# main.net
KiCad netlist of a schematic drawn in Altium Designer
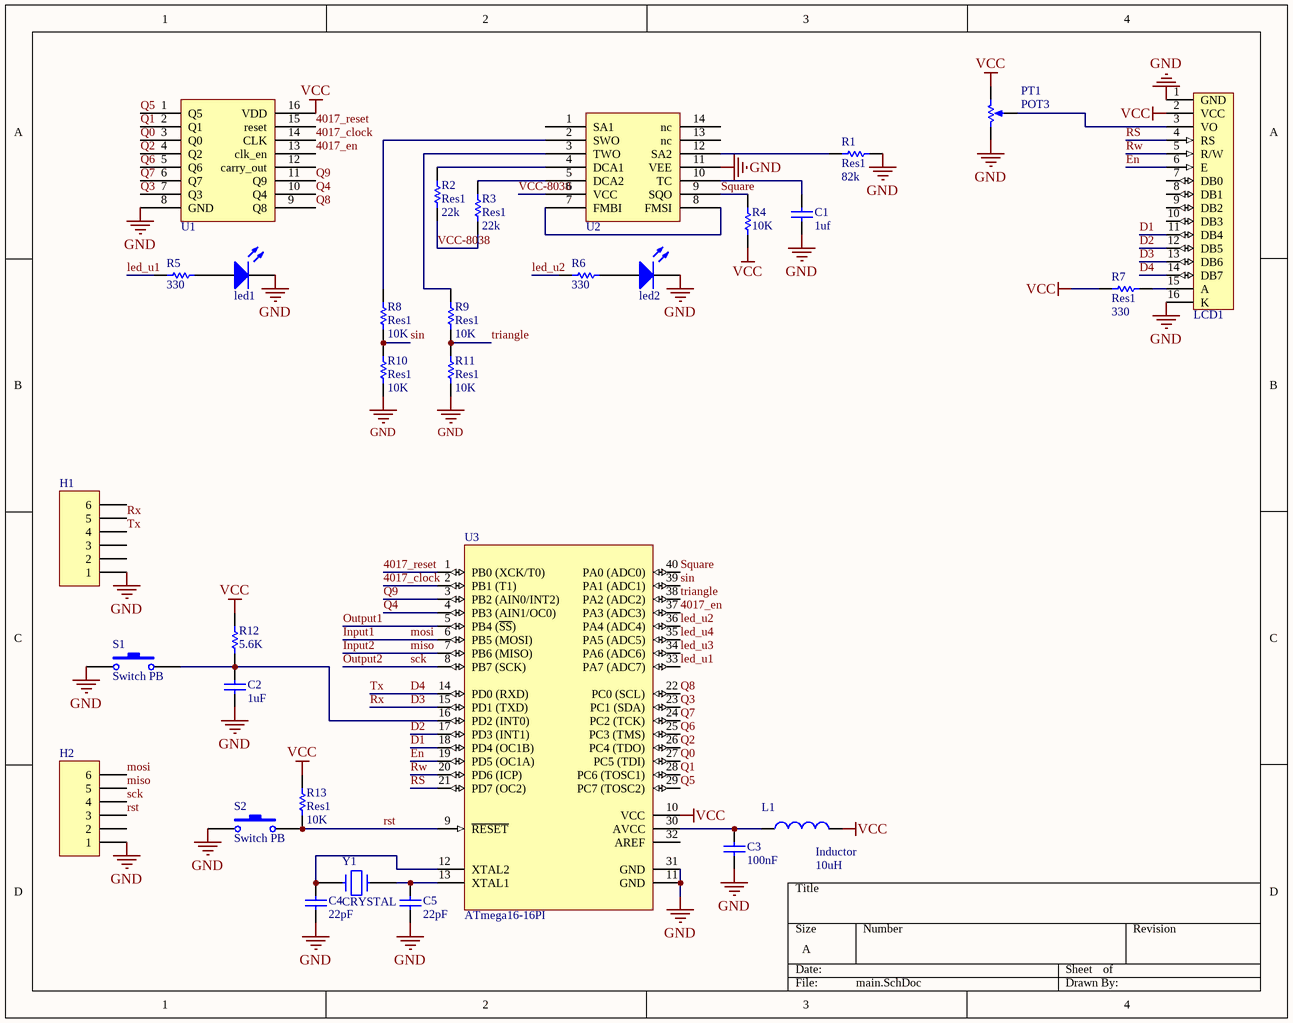
[diagram p0: main.SchDoc]

(export (version "E")
  (design (tool "Eeschema 10.0.6"))
  (components
    (comp (ref "C1")
      (value "1uf")
      (footprint "My_cap100n")
      (description "Capacitor")
      (fields (field (name "Comment") "Cap-NF") (field (name "PUBLISHER") "Altium Limited"))
      (libsource (lib "Mine-Discreet") (part "Cap-NF"))
    )
    (comp (ref "C2")
      (value "1uF")
      (footprint "My_cap100n")
      (description "Capacitor")
      (fields (field (name "Comment") "Cap-NF") (field (name "PUBLISHER") "Altium Limited"))
      (libsource (lib "Mine-Discreet") (part "Cap-NF"))
    )
    (comp (ref "C3")
      (value "100nF")
      (footprint "My_cap100n")
      (description "Capacitor")
      (fields (field (name "Comment") "Cap-NF") (field (name "PUBLISHER") "Altium Limited"))
      (libsource (lib "Mine-Discreet") (part "Cap-NF"))
    )
    (comp (ref "C4")
      (value "22pF")
      (footprint "My_cap100n")
      (description "Capacitor")
      (fields (field (name "Comment") "Cap-NF") (field (name "PUBLISHER") "Altium Limited"))
      (libsource (lib "Mine-Discreet") (part "Cap-NF"))
    )
    (comp (ref "C5")
      (value "22pF")
      (footprint "My_cap100n")
      (description "Capacitor")
      (fields (field (name "Comment") "Cap-NF") (field (name "PUBLISHER") "Altium Limited"))
      (libsource (lib "Mine-Discreet") (part "Cap-NF"))
    )
    (comp (ref "H1")
      (value "Header 6")
      (footprint "My_1X06")
      (description "Header, 6-Pin")
      (fields (field (name "PUBLISHER") "Altium Limited"))
      (libsource (lib "Altium library (www.AVRelec.com)") (part "Header 6"))
    )
    (comp (ref "H2")
      (value "Header 6")
      (footprint "My_1X06")
      (description "Header, 6-Pin")
      (fields (field (name "PUBLISHER") "Altium Limited"))
      (libsource (lib "Altium library (www.AVRelec.com)") (part "Header 6"))
    )
    (comp (ref "L1")
      (value "Inductor")
      (footprint "AXIAL-0.4")
      (fields (field (name "ALTIUM_VALUE") "10uH") (field (name "PUBLISHER") "Altium Limited"))
      (libsource (lib "Miscellaneous Devices") (part "Inductor"))
    )
    (comp (ref "LCD1")
      (value "LCD 16X2")
      (footprint "LCD 16x2")
      (description "LCD 16X2 Character lcd")
      (libsource (lib "Altium library (www.AVRelec.com)") (part "LCD 16X2"))
    )
    (comp (ref "led1")
      (value "LED 5mm")
      (footprint "Mine-Discreet:LED-5mm")
      (description "Typical LED")
      (fields (field (name "DESIGNER") "Seyed Mohsen Ghasemian") (field (name "PUBLISHER") "www.picpars.com"))
      (libsource (lib "PicPars.com_usefully_Library") (part "LED 5mm"))
    )
    (comp (ref "led2")
      (value "LED 5mm")
      (footprint "Mine-Discreet:LED-5mm")
      (description "Typical LED")
      (fields (field (name "DESIGNER") "Seyed Mohsen Ghasemian") (field (name "PUBLISHER") "www.picpars.com"))
      (libsource (lib "PicPars.com_usefully_Library") (part "LED 5mm"))
    )
    (comp (ref "PT1")
      (value "POT3")
      (footprint "POT3")
      (description "Variable Potentiometer top adjust")
      (fields (field (name "DESIGNER") "Seyed Mohsen Ghasemian"))
      (libsource (lib "PicPars.com_usefully_Library") (part "POT3"))
    )
    (comp (ref "R1")
      (value "Res1")
      (footprint "AXIAL-0.3")
      (description "Resistor")
      (fields (field (name "ALTIUM_VALUE") "82k") (field (name "PUBLISHER") "Altium Limited"))
      (libsource (lib "Miscellaneous Devices") (part "Res1"))
    )
    (comp (ref "R2")
      (value "Res1")
      (footprint "AXIAL-0.3")
      (description "Resistor")
      (fields (field (name "ALTIUM_VALUE") "22k") (field (name "PUBLISHER") "Altium Limited"))
      (libsource (lib "Miscellaneous Devices") (part "Res1"))
    )
    (comp (ref "R3")
      (value "Res1")
      (footprint "AXIAL-0.3")
      (description "Resistor")
      (fields (field (name "ALTIUM_VALUE") "22k") (field (name "PUBLISHER") "Altium Limited"))
      (libsource (lib "Miscellaneous Devices") (part "Res1"))
    )
    (comp (ref "R4")
      (value "10K")
      (footprint "AXIAL-0.3")
      (description "Resistor")
      (fields (field (name "Comment") "Res1") (field (name "PUBLISHER") "Altium Limited"))
      (libsource (lib "Miscellaneous Devices") (part "Res1"))
    )
    (comp (ref "R5")
      (value "330")
      (footprint "AXIAL-0.3")
      (description "Resistor")
      (fields (field (name "Comment") "Res1") (field (name "PUBLISHER") "Altium Limited"))
      (libsource (lib "Miscellaneous Devices") (part "Res1"))
    )
    (comp (ref "R6")
      (value "330")
      (footprint "AXIAL-0.3")
      (description "Resistor")
      (fields (field (name "Comment") "Res1") (field (name "PUBLISHER") "Altium Limited"))
      (libsource (lib "Miscellaneous Devices") (part "Res1"))
    )
    (comp (ref "R7")
      (value "Res1")
      (footprint "AXIAL-0.3")
      (description "Resistor")
      (fields (field (name "ALTIUM_VALUE") "330") (field (name "PUBLISHER") "Altium Limited"))
      (libsource (lib "Miscellaneous Devices") (part "Res1"))
    )
    (comp (ref "R8")
      (value "Res1")
      (footprint "AXIAL-0.3")
      (description "Resistor")
      (fields (field (name "ALTIUM_VALUE") "10K") (field (name "PUBLISHER") "Altium Limited"))
      (libsource (lib "Miscellaneous Devices") (part "Res1"))
    )
    (comp (ref "R9")
      (value "Res1")
      (footprint "AXIAL-0.3")
      (description "Resistor")
      (fields (field (name "ALTIUM_VALUE") "10K") (field (name "PUBLISHER") "Altium Limited"))
      (libsource (lib "Miscellaneous Devices") (part "Res1"))
    )
    (comp (ref "R10")
      (value "Res1")
      (footprint "AXIAL-0.3")
      (description "Resistor")
      (fields (field (name "ALTIUM_VALUE") "10K") (field (name "PUBLISHER") "Altium Limited"))
      (libsource (lib "Miscellaneous Devices") (part "Res1"))
    )
    (comp (ref "R11")
      (value "Res1")
      (footprint "AXIAL-0.3")
      (description "Resistor")
      (fields (field (name "ALTIUM_VALUE") "10K") (field (name "PUBLISHER") "Altium Limited"))
      (libsource (lib "Miscellaneous Devices") (part "Res1"))
    )
    (comp (ref "R12")
      (value "5.6K")
      (footprint "AXIAL-0.3")
      (description "Resistor")
      (fields (field (name "Comment") "Res1") (field (name "PUBLISHER") "Altium Limited"))
      (libsource (lib "Miscellaneous Devices") (part "Res1"))
    )
    (comp (ref "R13")
      (value "Res1")
      (footprint "AXIAL-0.3")
      (description "Resistor")
      (fields (field (name "ALTIUM_VALUE") "10K") (field (name "PUBLISHER") "Altium Limited"))
      (libsource (lib "Miscellaneous Devices") (part "Res1"))
    )
    (comp (ref "S1")
      (value "Switch PB")
      (footprint "Switch - Push to On")
      (description "Push Button Switch")
      (libsource (lib "My Library") (part "Switch PB"))
    )
    (comp (ref "S2")
      (value "Switch PB")
      (footprint "Switch - Push to On")
      (description "Push Button Switch")
      (libsource (lib "My Library") (part "Switch PB"))
    )
    (comp (ref "U1") (value "4017") (footprint "My Library:DIP16") (libsource (lib "Schlib1") (part "4017")))
    (comp (ref "U2")
      (value "xr8038")
      (footprint "My Library:DIP14")
      (libsource (lib "Schlib1") (part "xr8038"))
    )
    (comp (ref "U3")
      (value "ATmega16-16PI")
      (footprint "My_40P6")
      (description "AVR 16K Bytes of In-System Programmable Flash Memory")
      (fields (field (name "PUBLISHER") "Altium Limited"))
      (libsource (lib "Altium library (www.AVRelec.com)") (part "ATmega16-16PI"))
    )
    (comp (ref "Y1")
      (value "CRYSTAL")
      (footprint "My_Crystal")
      (description "Crystal")
      (libsource (lib "Altium library (www.AVRelec.com)") (part "CRYSTAL"))
    )
  )
  (nets
    (net (code "1") (name "/4017_clock") (class "Default")
      (node (ref "U1") (pin "14") (pinfunction "CLK_14") (pintype "power_in"))
      (node (ref "U3") (pin "2") (pinfunction "PB1_(T1)_2") (pintype "bidirectional"))
    )
    (net (code "2") (name "/4017_en") (class "Default")
      (node (ref "U1") (pin "13") (pinfunction "clk_en_13") (pintype "power_in"))
      (node (ref "U3") (pin "37") (pinfunction "PA3_(ADC3)_37") (pintype "bidirectional"))
    )
    (net (code "3") (name "/4017_reset") (class "Default")
      (node (ref "U1") (pin "15") (pinfunction "reset_15") (pintype "power_in"))
      (node (ref "U3") (pin "1") (pinfunction "PB0_(XCK/T0)_1") (pintype "bidirectional"))
    )
    (net (code "4") (name "/D1") (class "Default")
      (node (ref "LCD1") (pin "11") (pinfunction "DB4_11") (pintype "bidirectional"))
      (node (ref "U3") (pin "18") (pinfunction "PD4_(OC1B)_18") (pintype "bidirectional"))
    )
    (net (code "5") (name "/D2") (class "Default")
      (node (ref "LCD1") (pin "12") (pinfunction "DB5_12") (pintype "bidirectional"))
      (node (ref "U3") (pin "17") (pinfunction "PD3_(INT1)_17") (pintype "bidirectional"))
    )
    (net (code "6") (name "/D3") (class "Default")
      (node (ref "H1") (pin "5") (pinfunction "5_5") (pintype "passive"))
      (node (ref "LCD1") (pin "13") (pinfunction "DB6_13") (pintype "bidirectional"))
      (node (ref "U3") (pin "15") (pinfunction "PD1_(TXD)_15") (pintype "bidirectional"))
    )
    (net (code "7") (name "/D4") (class "Default")
      (node (ref "H1") (pin "4") (pinfunction "4_4") (pintype "passive"))
      (node (ref "LCD1") (pin "14") (pinfunction "DB7_14") (pintype "bidirectional"))
      (node (ref "U3") (pin "14") (pinfunction "PD0_(RXD)_14") (pintype "bidirectional"))
    )
    (net (code "8") (name "/En") (class "Default")
      (node (ref "LCD1") (pin "6") (pinfunction "E_6") (pintype "input"))
      (node (ref "U3") (pin "19") (pinfunction "PD5_(OC1A)_19") (pintype "bidirectional"))
    )
    (net (code "9") (name "/Input1") (class "Default")
      (node (ref "H2") (pin "6") (pinfunction "6_6") (pintype "passive"))
      (node (ref "U3") (pin "6") (pinfunction "PB5_(MOSI)_6") (pintype "bidirectional"))
    )
    (net (code "10") (name "/Input2") (class "Default")
      (node (ref "H2") (pin "5") (pinfunction "5_5") (pintype "passive"))
      (node (ref "U3") (pin "7") (pinfunction "PB6_(MISO)_7") (pintype "bidirectional"))
    )
    (net (code "11") (name "/Output1") (class "Default")
      (node (ref "U3") (pin "5") (pinfunction "PB4_(~{SS})_5") (pintype "bidirectional"))
    )
    (net (code "12") (name "/Output2") (class "Default")
      (node (ref "H2") (pin "4") (pinfunction "4_4") (pintype "passive"))
      (node (ref "U3") (pin "8") (pinfunction "PB7_(SCK)_8") (pintype "bidirectional"))
    )
    (net (code "13") (name "/Q0") (class "Default")
      (node (ref "U1") (pin "3") (pinfunction "Q0_3") (pintype "power_in"))
      (node (ref "U3") (pin "27") (pinfunction "PC5_(TDI)_27") (pintype "bidirectional"))
    )
    (net (code "14") (name "/Q1") (class "Default")
      (node (ref "U1") (pin "2") (pinfunction "Q1_2") (pintype "power_in"))
      (node (ref "U3") (pin "28") (pinfunction "PC6_(TOSC1)_28") (pintype "bidirectional"))
    )
    (net (code "15") (name "/Q2") (class "Default")
      (node (ref "U1") (pin "4") (pinfunction "Q2_4") (pintype "power_in"))
      (node (ref "U3") (pin "26") (pinfunction "PC4_(TDO)_26") (pintype "bidirectional"))
    )
    (net (code "16") (name "/Q3") (class "Default")
      (node (ref "U1") (pin "7") (pinfunction "Q3_7") (pintype "power_in"))
      (node (ref "U3") (pin "23") (pinfunction "PC1_(SDA)_23") (pintype "bidirectional"))
    )
    (net (code "17") (name "/Q4") (class "Default")
      (node (ref "U1") (pin "10") (pinfunction "Q4_10") (pintype "power_in"))
      (node (ref "U3") (pin "4") (pinfunction "PB3_(AIN1/OC0)_4") (pintype "bidirectional"))
    )
    (net (code "18") (name "/Q5") (class "Default")
      (node (ref "U1") (pin "1") (pinfunction "Q5_1") (pintype "power_in"))
      (node (ref "U3") (pin "29") (pinfunction "PC7_(TOSC2)_29") (pintype "bidirectional"))
    )
    (net (code "19") (name "/Q6") (class "Default")
      (node (ref "U1") (pin "5") (pinfunction "Q6_5") (pintype "power_in"))
      (node (ref "U3") (pin "25") (pinfunction "PC3_(TMS)_25") (pintype "bidirectional"))
    )
    (net (code "20") (name "/Q7") (class "Default")
      (node (ref "U1") (pin "6") (pinfunction "Q7_6") (pintype "power_in"))
      (node (ref "U3") (pin "24") (pinfunction "PC2_(TCK)_24") (pintype "bidirectional"))
    )
    (net (code "21") (name "/Q8") (class "Default")
      (node (ref "U1") (pin "9") (pinfunction "Q8_9") (pintype "power_in"))
      (node (ref "U3") (pin "22") (pinfunction "PC0_(SCL)_22") (pintype "bidirectional"))
    )
    (net (code "22") (name "/Q9") (class "Default")
      (node (ref "U1") (pin "11") (pinfunction "Q9_11") (pintype "power_in"))
      (node (ref "U3") (pin "3") (pinfunction "PB2_(AIN0/INT2)_3") (pintype "bidirectional"))
    )
    (net (code "23") (name "/RS") (class "Default")
      (node (ref "LCD1") (pin "4") (pinfunction "RS_4") (pintype "input"))
      (node (ref "U3") (pin "21") (pinfunction "PD7_(OC2)_21") (pintype "bidirectional"))
    )
    (net (code "24") (name "/Rw") (class "Default")
      (node (ref "LCD1") (pin "5") (pinfunction "R/W_5") (pintype "input"))
      (node (ref "U3") (pin "20") (pinfunction "PD6_(ICP)_20") (pintype "bidirectional"))
    )
    (net (code "25") (name "/Square") (class "Default")
      (node (ref "R4") (pin "2") (pinfunction "2_2") (pintype "passive"))
      (node (ref "U2") (pin "9") (pinfunction "SQO_9") (pintype "power_in"))
      (node (ref "U3") (pin "40") (pinfunction "PA0_(ADC0)_40") (pintype "bidirectional"))
    )
    (net (code "26") (name "/VCC-8038") (class "Default")
      (node (ref "R2") (pin "1") (pinfunction "1_1") (pintype "passive"))
      (node (ref "R3") (pin "1") (pinfunction "1_1") (pintype "passive"))
      (node (ref "U2") (pin "6") (pinfunction "VCC_6") (pintype "power_in"))
    )
    (net (code "27") (name "/led_u1") (class "Default")
      (node (ref "R5") (pin "1") (pinfunction "1_1") (pintype "passive"))
      (node (ref "U3") (pin "33") (pinfunction "PA7_(ADC7)_33") (pintype "bidirectional"))
    )
    (net (code "28") (name "/led_u2") (class "Default")
      (node (ref "R6") (pin "1") (pinfunction "1_1") (pintype "passive"))
      (node (ref "U3") (pin "36") (pinfunction "PA4_(ADC4)_36") (pintype "bidirectional"))
    )
    (net (code "29") (name "/led_u3") (class "Default")
      (node (ref "U3") (pin "34") (pinfunction "PA6_(ADC6)_34") (pintype "bidirectional"))
    )
    (net (code "30") (name "/led_u4") (class "Default")
      (node (ref "U3") (pin "35") (pinfunction "PA5_(ADC5)_35") (pintype "bidirectional"))
    )
    (net (code "31") (name "/rst") (class "Default")
      (node (ref "H2") (pin "3") (pinfunction "3_3") (pintype "passive"))
      (node (ref "R13") (pin "1") (pinfunction "1_1") (pintype "passive"))
      (node (ref "S2") (pin "2") (pinfunction "2_2") (pintype "passive"))
      (node (ref "U3") (pin "9") (pinfunction "~{RESET}_9") (pintype "input"))
    )
    (net (code "32") (name "/sin") (class "Default")
      (node (ref "R10") (pin "2") (pinfunction "2_2") (pintype "passive"))
      (node (ref "R8") (pin "1") (pinfunction "1_1") (pintype "passive"))
      (node (ref "U3") (pin "39") (pinfunction "PA1_(ADC1)_39") (pintype "bidirectional"))
    )
    (net (code "33") (name "/triangle") (class "Default")
      (node (ref "R11") (pin "2") (pinfunction "2_2") (pintype "passive"))
      (node (ref "R9") (pin "1") (pinfunction "1_1") (pintype "passive"))
      (node (ref "U3") (pin "38") (pinfunction "PA2_(ADC2)_38") (pintype "bidirectional"))
    )
    (net (code "34") (name "GND") (class "Default")
      (node (ref "C1") (pin "1") (pinfunction "1_1") (pintype "passive"))
      (node (ref "C2") (pin "1") (pinfunction "1_1") (pintype "passive"))
      (node (ref "C3") (pin "2") (pinfunction "2_2") (pintype "passive"))
      (node (ref "C4") (pin "2") (pinfunction "2_2") (pintype "passive"))
      (node (ref "C5") (pin "2") (pinfunction "2_2") (pintype "passive"))
      (node (ref "H1") (pin "1") (pinfunction "1_1") (pintype "passive"))
      (node (ref "H2") (pin "1") (pinfunction "1_1") (pintype "passive"))
      (node (ref "LCD1") (pin "1") (pinfunction "GND_1") (pintype "power_in"))
      (node (ref "LCD1") (pin "16") (pinfunction "K_16") (pintype "passive"))
      (node (ref "PT1") (pin "2") (pinfunction "BOT_2") (pintype "passive"))
      (node (ref "R1") (pin "2") (pinfunction "2_2") (pintype "passive"))
      (node (ref "R10") (pin "1") (pinfunction "1_1") (pintype "passive"))
      (node (ref "R11") (pin "1") (pinfunction "1_1") (pintype "passive"))
      (node (ref "S1") (pin "1") (pinfunction "1_1") (pintype "passive"))
      (node (ref "S2") (pin "1") (pinfunction "1_1") (pintype "passive"))
      (node (ref "U1") (pin "8") (pinfunction "GND_8") (pintype "power_in"))
      (node (ref "U2") (pin "11") (pinfunction "VEE_11") (pintype "power_in"))
      (node (ref "U3") (pin "11") (pinfunction "GND_11") (pintype "power_in"))
      (node (ref "U3") (pin "31") (pinfunction "GND_31") (pintype "power_in"))
      (node (ref "led1") (pin "2") (pinfunction "K_2") (pintype "passive"))
      (node (ref "led2") (pin "2") (pinfunction "K_2") (pintype "passive"))
    )
    (net (code "35") (name "Net-(LCD1-A)") (class "Default")
      (node (ref "LCD1") (pin "15") (pinfunction "A_15") (pintype "passive"))
      (node (ref "R7") (pin "2") (pinfunction "2_2") (pintype "passive"))
    )
    (net (code "36") (name "Net-(LCD1-VO)") (class "Default")
      (node (ref "LCD1") (pin "3") (pinfunction "VO_3") (pintype "passive"))
      (node (ref "PT1") (pin "3") (pinfunction "TAP_3") (pintype "passive"))
    )
    (net (code "37") (name "Net-(U2-DCA1)") (class "Default")
      (node (ref "R2") (pin "2") (pinfunction "2_2") (pintype "passive"))
      (node (ref "U2") (pin "4") (pinfunction "DCA1_4") (pintype "power_in"))
    )
    (net (code "38") (name "Net-(U2-DCA2)") (class "Default")
      (node (ref "R3") (pin "2") (pinfunction "2_2") (pintype "passive"))
      (node (ref "U2") (pin "5") (pinfunction "DCA2_5") (pintype "power_in"))
    )
    (net (code "39") (name "Net-(U2-FMBI)") (class "Default")
      (node (ref "U2") (pin "7") (pinfunction "FMBI_7") (pintype "power_in"))
      (node (ref "U2") (pin "8") (pinfunction "FMSI_8") (pintype "power_in"))
    )
    (net (code "40") (name "Net-(U2-SA2)") (class "Default")
      (node (ref "R1") (pin "1") (pinfunction "1_1") (pintype "passive"))
      (node (ref "U2") (pin "12") (pinfunction "SA2_12") (pintype "power_in"))
    )
    (net (code "41") (name "Net-(U2-SWO)") (class "Default")
      (node (ref "R8") (pin "2") (pinfunction "2_2") (pintype "passive"))
      (node (ref "U2") (pin "2") (pinfunction "SWO_2") (pintype "power_in"))
    )
    (net (code "42") (name "Net-(U2-TC)") (class "Default")
      (node (ref "C1") (pin "2") (pinfunction "2_2") (pintype "passive"))
      (node (ref "U2") (pin "10") (pinfunction "TC_10") (pintype "power_in"))
    )
    (net (code "43") (name "Net-(U2-TWO)") (class "Default")
      (node (ref "R9") (pin "2") (pinfunction "2_2") (pintype "passive"))
      (node (ref "U2") (pin "3") (pinfunction "TWO_3") (pintype "power_in"))
    )
    (net (code "44") (name "Net-(U3-AVCC)") (class "Default")
      (node (ref "C3") (pin "1") (pinfunction "1_1") (pintype "passive"))
      (node (ref "L1") (pin "1") (pinfunction "1_1") (pintype "passive"))
      (node (ref "U3") (pin "30") (pinfunction "AVCC_30") (pintype "power_in"))
    )
    (net (code "45") (name "Net-(U3-PD2_(INT0))") (class "Default")
      (node (ref "C2") (pin "2") (pinfunction "2_2") (pintype "passive"))
      (node (ref "R12") (pin "2") (pinfunction "2_2") (pintype "passive"))
      (node (ref "S1") (pin "2") (pinfunction "2_2") (pintype "passive"))
      (node (ref "U3") (pin "16") (pinfunction "PD2_(INT0)_16") (pintype "bidirectional"))
    )
    (net (code "46") (name "Net-(U3-XTAL1)") (class "Default")
      (node (ref "C5") (pin "1") (pinfunction "1_1") (pintype "passive"))
      (node (ref "U3") (pin "13") (pinfunction "XTAL1_13") (pintype "passive"))
      (node (ref "Y1") (pin "2") (pinfunction "2_2") (pintype "passive"))
    )
    (net (code "47") (name "Net-(U3-XTAL2)") (class "Default")
      (node (ref "C4") (pin "1") (pinfunction "1_1") (pintype "passive"))
      (node (ref "U3") (pin "12") (pinfunction "XTAL2_12") (pintype "passive"))
      (node (ref "Y1") (pin "1") (pinfunction "1_1") (pintype "passive"))
    )
    (net (code "48") (name "Net-(led1-A)") (class "Default")
      (node (ref "R5") (pin "2") (pinfunction "2_2") (pintype "passive"))
      (node (ref "led1") (pin "1") (pinfunction "A_1") (pintype "passive"))
    )
    (net (code "49") (name "Net-(led2-A)") (class "Default")
      (node (ref "R6") (pin "2") (pinfunction "2_2") (pintype "passive"))
      (node (ref "led2") (pin "1") (pinfunction "A_1") (pintype "passive"))
    )
    (net (code "50") (name "VCC") (class "Default")
      (node (ref "L1") (pin "2") (pinfunction "2_2") (pintype "passive"))
      (node (ref "LCD1") (pin "2") (pinfunction "VCC_2") (pintype "power_in"))
      (node (ref "PT1") (pin "1") (pinfunction "TOP_1") (pintype "passive"))
      (node (ref "R12") (pin "1") (pinfunction "1_1") (pintype "passive"))
      (node (ref "R13") (pin "2") (pinfunction "2_2") (pintype "passive"))
      (node (ref "R4") (pin "1") (pinfunction "1_1") (pintype "passive"))
      (node (ref "R7") (pin "1") (pinfunction "1_1") (pintype "passive"))
      (node (ref "U1") (pin "16") (pinfunction "VDD_16") (pintype "power_in"))
      (node (ref "U3") (pin "10") (pinfunction "VCC_10") (pintype "power_in"))
    )
    (net (code "51") (name "unconnected-(H1-Pad2)") (class "Default")
      (node (ref "H1") (pin "2") (pinfunction "2_2") (pintype "passive"))
    )
    (net (code "52") (name "unconnected-(H1-Pad3)") (class "Default")
      (node (ref "H1") (pin "3") (pinfunction "3_3") (pintype "passive"))
    )
    (net (code "53") (name "unconnected-(H1-Pad6)") (class "Default")
      (node (ref "H1") (pin "6") (pinfunction "6_6") (pintype "passive"))
    )
    (net (code "54") (name "unconnected-(H2-Pad2)") (class "Default")
      (node (ref "H2") (pin "2") (pinfunction "2_2") (pintype "passive"))
    )
    (net (code "55") (name "unconnected-(LCD1-DB0-Pad7)") (class "Default")
      (node (ref "LCD1") (pin "7") (pinfunction "DB0_7") (pintype "bidirectional"))
    )
    (net (code "56") (name "unconnected-(LCD1-DB1-Pad8)") (class "Default")
      (node (ref "LCD1") (pin "8") (pinfunction "DB1_8") (pintype "bidirectional"))
    )
    (net (code "57") (name "unconnected-(LCD1-DB2-Pad9)") (class "Default")
      (node (ref "LCD1") (pin "9") (pinfunction "DB2_9") (pintype "bidirectional"))
    )
    (net (code "58") (name "unconnected-(LCD1-DB3-Pad10)") (class "Default")
      (node (ref "LCD1") (pin "10") (pinfunction "DB3_10") (pintype "bidirectional"))
    )
    (net (code "59") (name "unconnected-(U1-carry_out-Pad12)") (class "Default")
      (node (ref "U1") (pin "12") (pinfunction "carry_out_12") (pintype "power_in"))
    )
    (net (code "60") (name "unconnected-(U2-SA1-Pad1)") (class "Default")
      (node (ref "U2") (pin "1") (pinfunction "SA1_1") (pintype "power_in"))
    )
    (net (code "61") (name "unconnected-(U2-nc-Pad13)") (class "Default")
      (node (ref "U2") (pin "13") (pinfunction "nc_13") (pintype "power_in"))
    )
    (net (code "62") (name "unconnected-(U2-nc-Pad14)") (class "Default")
      (node (ref "U2") (pin "14") (pinfunction "nc_14") (pintype "power_in"))
    )
    (net (code "63") (name "unconnected-(U3-AREF-Pad32)") (class "Default")
      (node (ref "U3") (pin "32") (pinfunction "AREF_32") (pintype "passive"))
    )
  )
)
